# Stepper_Test.net
KiCad netlist of a schematic drawn in EAGLE
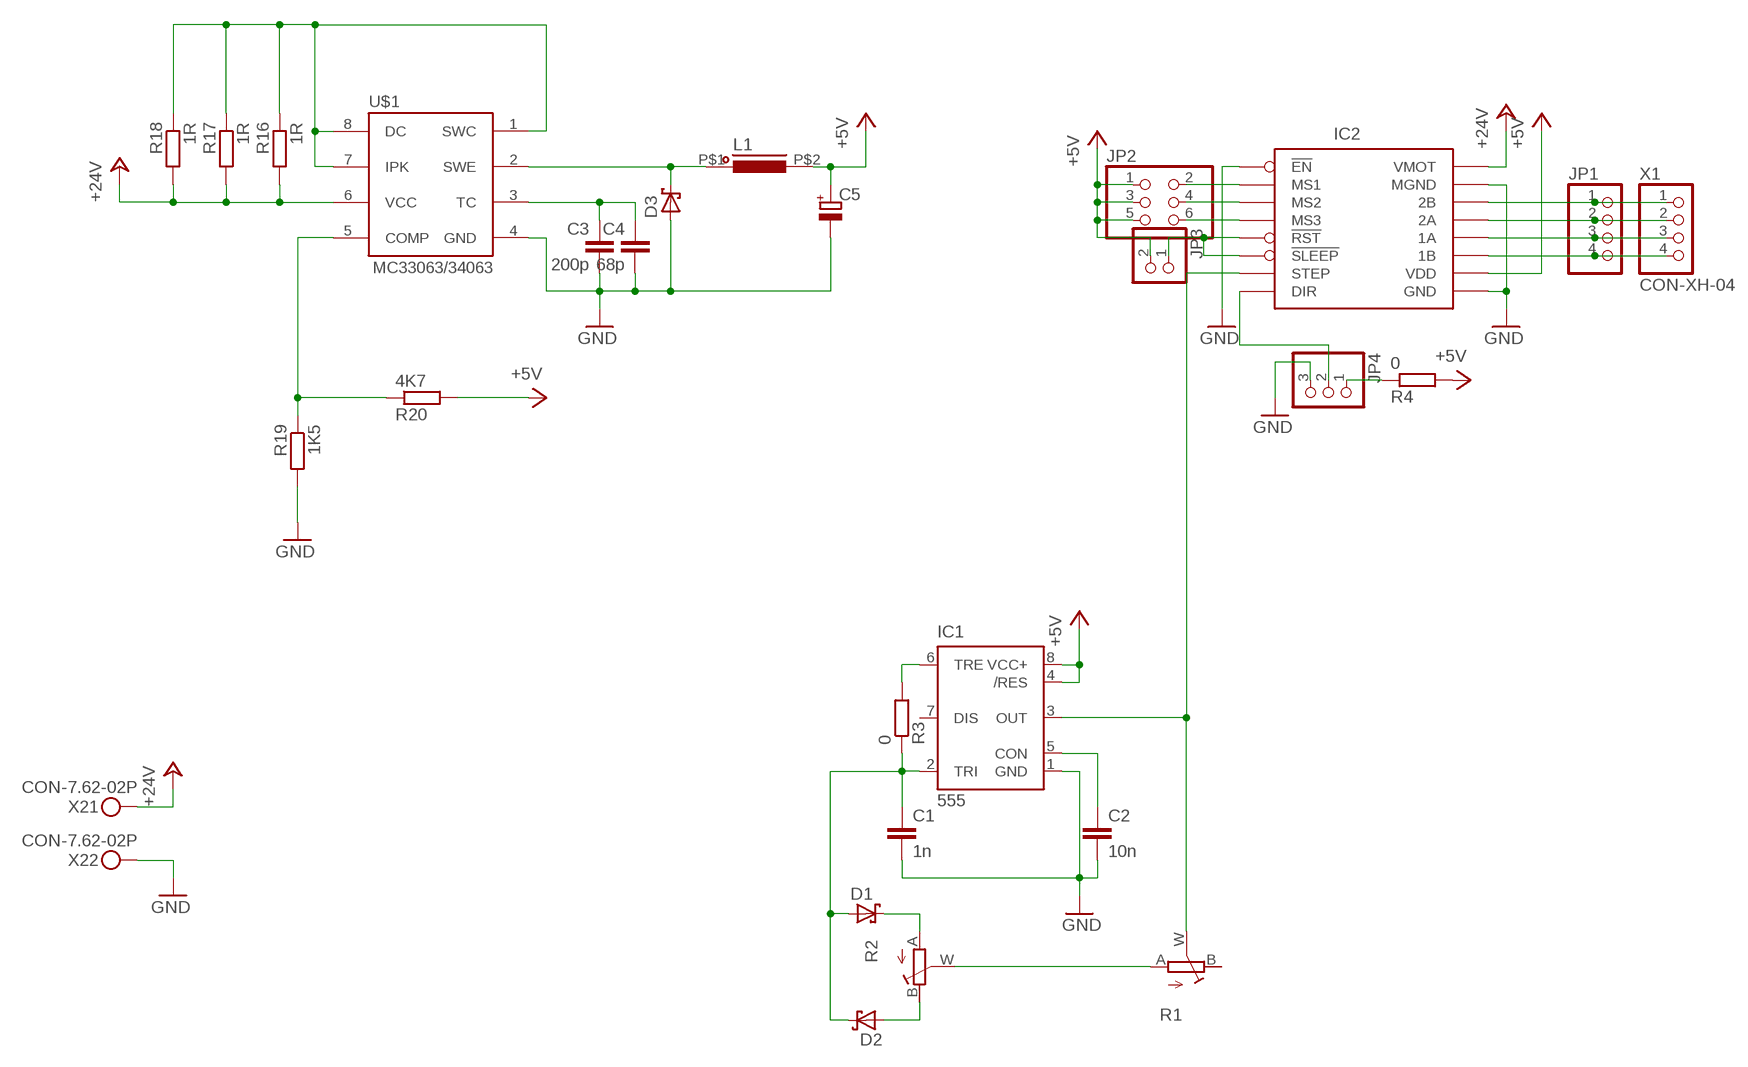
[diagram p0: schematic, sheet 1]

(export (version "E")
  (design (tool "Eeschema 10.0.6"))
  (components
    (comp (ref "C1")
      (value "1n")
      (footprint "eagle-import:C0805")
      (libsource (lib "eagle-import") (part "CAP_0805"))
    )
    (comp (ref "C2")
      (value "10n")
      (footprint "eagle-import:C0805")
      (libsource (lib "eagle-import") (part "CAP_0805"))
    )
    (comp (ref "C3")
      (value "200p")
      (footprint "eagle-import:C0805")
      (libsource (lib "eagle-import") (part "Namenlos_CAP_0805"))
    )
    (comp (ref "C4")
      (value "68p")
      (footprint "eagle-import:C0805")
      (libsource (lib "eagle-import") (part "Namenlos_CAP_0805"))
    )
    (comp (ref "C5")
      (value "CAP-POL_E3.5-8")
      (footprint "eagle-import:E3,5-8")
      (libsource (lib "eagle-import") (part "CAP-POL_E3.5-8"))
    )
    (comp (ref "D1")
      (value "DIODE-SH_SOD523")
      (footprint "eagle-import:SOD523")
      (libsource (lib "eagle-import") (part "DIODE-SH_SOD523"))
    )
    (comp (ref "D2")
      (value "DIODE-SH_SOD523")
      (footprint "eagle-import:SOD523")
      (libsource (lib "eagle-import") (part "DIODE-SH_SOD523"))
    )
    (comp (ref "D3")
      (value "DIODE-SH_SMA")
      (footprint "eagle-import:DO214AC")
      (libsource (lib "eagle-import") (part "Namenlos_DIODE-SH_SMA"))
    )
    (comp (ref "IC1")
      (value "555")
      (footprint "eagle-import:SO08")
      (libsource (lib "eagle-import") (part "555D"))
    )
    (comp (ref "IC2")
      (value "STEP-DRV")
      (footprint "eagle-import:DRV-BRK")
      (libsource (lib "eagle-import") (part "STEP-DRV"))
    )
    (comp (ref "JP1")
      (value "PINHD-1X4")
      (footprint "eagle-import:1X04")
      (libsource (lib "eagle-import") (part "PINHD-1X4"))
    )
    (comp (ref "JP2")
      (value "PINHD-2X3")
      (footprint "eagle-import:2X03")
      (libsource (lib "eagle-import") (part "PINHD-2X3"))
    )
    (comp (ref "JP3")
      (value "PINHD-1X2")
      (footprint "eagle-import:1X02")
      (libsource (lib "eagle-import") (part "PINHD-1X2"))
    )
    (comp (ref "JP4")
      (value "PINHD-1X3")
      (footprint "eagle-import:1X03")
      (libsource (lib "eagle-import") (part "PINHD-1X3"))
    )
    (comp (ref "L1")
      (value "INDUCTORCW68")
      (footprint "eagle-import:CW68")
      (libsource (lib "eagle-import") (part "INDUCTORCW68"))
    )
    (comp (ref "R1")
      (value "R_POTTURN-X")
      (footprint "eagle-import:RJ9W")
      (libsource (lib "eagle-import") (part "R_POTTURN-X"))
    )
    (comp (ref "R2")
      (value "R_POTTURN-X")
      (footprint "eagle-import:RJ9W")
      (libsource (lib "eagle-import") (part "R_POTTURN-X"))
    )
    (comp (ref "R3")
      (value "0")
      (footprint "eagle-import:R0805")
      (libsource (lib "eagle-import") (part "R_0805"))
    )
    (comp (ref "R4")
      (value "0")
      (footprint "eagle-import:R0805")
      (libsource (lib "eagle-import") (part "R_0805"))
    )
    (comp (ref "R16")
      (value "1R")
      (footprint "eagle-import:R0805")
      (libsource (lib "eagle-import") (part "R_0805"))
    )
    (comp (ref "R17")
      (value "1R")
      (footprint "eagle-import:R0805")
      (libsource (lib "eagle-import") (part "R_0805"))
    )
    (comp (ref "R18")
      (value "1R")
      (footprint "eagle-import:R0805")
      (libsource (lib "eagle-import") (part "R_0805"))
    )
    (comp (ref "R19")
      (value "1K5")
      (footprint "eagle-import:R0805")
      (libsource (lib "eagle-import") (part "R_0805"))
    )
    (comp (ref "R20")
      (value "4K7")
      (footprint "eagle-import:R0805")
      (libsource (lib "eagle-import") (part "R_0805"))
    )
    (comp (ref "U$1")
      (value "MC33063/MC34063P")
      (footprint "eagle-import:DIL08")
      (libsource (lib "eagle-import") (part "MC33063/MC34063P"))
    )
    (comp (ref "X1")
      (value "CON-XH-04")
      (footprint "eagle-import:XH-04")
      (libsource (lib "eagle-import") (part "CON-XH-04"))
    )
    (comp (ref "X2")
      (value "CON-7.62-02P")
      (footprint "eagle-import:KF25C-7.62-02P-13")
      (libsource (lib "eagle-import") (part "CON-7.62-02P"))
    )
  )
  (nets
    (net (code "1") (name "+5V") (class "Default")
      (node (ref "C5") (pin "+") (pinfunction "+_+") (pintype "passive"))
      (node (ref "IC1") (pin "4") (pinfunction "/RES_4") (pintype "input"))
      (node (ref "IC1") (pin "8") (pinfunction "VCC+_8") (pintype "power_in"))
      (node (ref "IC2") (pin "P$10") (pinfunction "VDD_P$10") (pintype "bidirectional"))
      (node (ref "JP2") (pin "1") (pinfunction "1_1") (pintype "passive"))
      (node (ref "JP2") (pin "3") (pinfunction "3_3") (pintype "passive"))
      (node (ref "JP2") (pin "5") (pinfunction "5_5") (pintype "passive"))
      (node (ref "JP3") (pin "2") (pinfunction "2_2") (pintype "passive"))
      (node (ref "L1") (pin "P$2") (pinfunction "2_P$2") (pintype "passive"))
      (node (ref "R20") (pin "2") (pinfunction "2_2") (pintype "passive"))
      (node (ref "R4") (pin "2") (pinfunction "2_2") (pintype "passive"))
    )
    (net (code "2") (name "+24V") (class "Default")
      (node (ref "IC2") (pin "P$16") (pinfunction "VMOT_P$16") (pintype "bidirectional"))
      (node (ref "R16") (pin "2") (pinfunction "2_2") (pintype "passive"))
      (node (ref "R17") (pin "2") (pinfunction "2_2") (pintype "passive"))
      (node (ref "R18") (pin "2") (pinfunction "2_2") (pintype "passive"))
      (node (ref "U$1") (pin "6") (pinfunction "VCC_6") (pintype "power_in"))
      (node (ref "X2") (pin "P$1") (pinfunction "KL_P$1") (pintype "passive"))
    )
    (net (code "3") (name "GND") (class "Default")
      (node (ref "C1") (pin "2") (pinfunction "2_2") (pintype "passive"))
      (node (ref "C2") (pin "2") (pinfunction "2_2") (pintype "passive"))
      (node (ref "C3") (pin "2") (pinfunction "2_2") (pintype "passive"))
      (node (ref "C4") (pin "2") (pinfunction "2_2") (pintype "passive"))
      (node (ref "C5") (pin "-") (pinfunction "-_-") (pintype "passive"))
      (node (ref "D3") (pin "A") (pinfunction "A_A") (pintype "passive"))
      (node (ref "IC1") (pin "1") (pinfunction "GND_1") (pintype "power_in"))
      (node (ref "IC2") (pin "P$1") (pinfunction "~{EN}_P$1") (pintype "bidirectional"))
      (node (ref "IC2") (pin "P$15") (pinfunction "MGND_P$15") (pintype "bidirectional"))
      (node (ref "IC2") (pin "P$9") (pinfunction "GND_P$9") (pintype "bidirectional"))
      (node (ref "JP4") (pin "3") (pinfunction "3_3") (pintype "passive"))
      (node (ref "R19") (pin "2") (pinfunction "2_2") (pintype "passive"))
      (node (ref "U$1") (pin "4") (pinfunction "GND_4") (pintype "power_in"))
      (node (ref "X2") (pin "P$2") (pinfunction "KL_P$2") (pintype "passive"))
    )
    (net (code "4") (name "Net-(D1-PadC)") (class "Default")
      (node (ref "D1") (pin "C") (pinfunction "C_C") (pintype "passive"))
      (node (ref "R2") (pin "A") (pinfunction "A_A") (pintype "passive"))
    )
    (net (code "5") (name "Net-(IC1-CON)") (class "Default")
      (node (ref "C2") (pin "1") (pinfunction "1_1") (pintype "passive"))
      (node (ref "IC1") (pin "5") (pinfunction "CON_5") (pintype "input"))
    )
    (net (code "6") (name "Net-(IC1-OUT)") (class "Default")
      (node (ref "IC1") (pin "3") (pinfunction "OUT_3") (pintype "output"))
      (node (ref "IC2") (pin "P$7") (pinfunction "STEP_P$7") (pintype "bidirectional"))
      (node (ref "R1") (pin "W") (pinfunction "S_W") (pintype "passive"))
    )
    (net (code "7") (name "Net-(IC1-TRE)") (class "Default")
      (node (ref "IC1") (pin "6") (pinfunction "TRE_6") (pintype "input"))
      (node (ref "R3") (pin "2") (pinfunction "2_2") (pintype "passive"))
    )
    (net (code "8") (name "Net-(IC1-TRI)") (class "Default")
      (node (ref "C1") (pin "1") (pinfunction "1_1") (pintype "passive"))
      (node (ref "D1") (pin "A") (pinfunction "A_A") (pintype "passive"))
      (node (ref "D2") (pin "C") (pinfunction "C_C") (pintype "passive"))
      (node (ref "IC1") (pin "2") (pinfunction "TRI_2") (pintype "input"))
      (node (ref "R3") (pin "1") (pinfunction "1_1") (pintype "passive"))
    )
    (net (code "9") (name "Net-(IC2-1A)") (class "Default")
      (node (ref "IC2") (pin "P$12") (pinfunction "1A_P$12") (pintype "bidirectional"))
      (node (ref "JP1") (pin "3") (pinfunction "3_3") (pintype "passive"))
      (node (ref "X1") (pin "3") (pinfunction "3_3") (pintype "passive"))
    )
    (net (code "10") (name "Net-(IC2-1B)") (class "Default")
      (node (ref "IC2") (pin "P$11") (pinfunction "1B_P$11") (pintype "bidirectional"))
      (node (ref "JP1") (pin "4") (pinfunction "4_4") (pintype "passive"))
      (node (ref "X1") (pin "4") (pinfunction "4_4") (pintype "passive"))
    )
    (net (code "11") (name "Net-(IC2-2A)") (class "Default")
      (node (ref "IC2") (pin "P$13") (pinfunction "2A_P$13") (pintype "bidirectional"))
      (node (ref "JP1") (pin "2") (pinfunction "2_2") (pintype "passive"))
      (node (ref "X1") (pin "2") (pinfunction "2_2") (pintype "passive"))
    )
    (net (code "12") (name "Net-(IC2-2B)") (class "Default")
      (node (ref "IC2") (pin "P$14") (pinfunction "2B_P$14") (pintype "bidirectional"))
      (node (ref "JP1") (pin "1") (pinfunction "1_1") (pintype "passive"))
      (node (ref "X1") (pin "1") (pinfunction "1_1") (pintype "passive"))
    )
    (net (code "13") (name "Net-(IC2-DIR)") (class "Default")
      (node (ref "IC2") (pin "P$8") (pinfunction "DIR_P$8") (pintype "bidirectional"))
      (node (ref "JP4") (pin "2") (pinfunction "2_2") (pintype "passive"))
    )
    (net (code "14") (name "Net-(IC2-MS1)") (class "Default")
      (node (ref "IC2") (pin "P$2") (pinfunction "MS1_P$2") (pintype "bidirectional"))
      (node (ref "JP2") (pin "2") (pinfunction "2_2") (pintype "passive"))
    )
    (net (code "15") (name "Net-(IC2-MS2)") (class "Default")
      (node (ref "IC2") (pin "P$3") (pinfunction "MS2_P$3") (pintype "bidirectional"))
      (node (ref "JP2") (pin "4") (pinfunction "4_4") (pintype "passive"))
    )
    (net (code "16") (name "Net-(IC2-MS3)") (class "Default")
      (node (ref "IC2") (pin "P$4") (pinfunction "MS3_P$4") (pintype "bidirectional"))
      (node (ref "JP2") (pin "6") (pinfunction "6_6") (pintype "passive"))
    )
    (net (code "17") (name "Net-(IC2-~{RST})") (class "Default")
      (node (ref "IC2") (pin "P$5") (pinfunction "~{RST}_P$5") (pintype "bidirectional"))
      (node (ref "IC2") (pin "P$6") (pinfunction "~{SLEEP}_P$6") (pintype "bidirectional"))
      (node (ref "JP3") (pin "1") (pinfunction "1_1") (pintype "passive"))
    )
    (net (code "18") (name "Net-(JP4-Pad1)") (class "Default")
      (node (ref "JP4") (pin "1") (pinfunction "1_1") (pintype "passive"))
      (node (ref "R4") (pin "1") (pinfunction "1_1") (pintype "passive"))
    )
    (net (code "19") (name "Net-(L1-1)") (class "Default")
      (node (ref "D3") (pin "C") (pinfunction "C_C") (pintype "passive"))
      (node (ref "L1") (pin "P$1") (pinfunction "1_P$1") (pintype "passive"))
      (node (ref "U$1") (pin "2") (pinfunction "SWE_2") (pintype "input"))
    )
    (net (code "20") (name "Net-(R2-E)") (class "Default")
      (node (ref "D2") (pin "A") (pinfunction "A_A") (pintype "passive"))
      (node (ref "R2") (pin "B") (pinfunction "E_B") (pintype "passive"))
    )
    (net (code "21") (name "Net-(R2-S)") (class "Default")
      (node (ref "R1") (pin "A") (pinfunction "A_A") (pintype "passive"))
      (node (ref "R2") (pin "W") (pinfunction "S_W") (pintype "passive"))
    )
    (net (code "22") (name "Net-(U$1-COMP)") (class "Default")
      (node (ref "R19") (pin "1") (pinfunction "1_1") (pintype "passive"))
      (node (ref "R20") (pin "1") (pinfunction "1_1") (pintype "passive"))
      (node (ref "U$1") (pin "5") (pinfunction "COMP_5") (pintype "input"))
    )
    (net (code "23") (name "Net-(U$1-DC)") (class "Default")
      (node (ref "R16") (pin "1") (pinfunction "1_1") (pintype "passive"))
      (node (ref "R17") (pin "1") (pinfunction "1_1") (pintype "passive"))
      (node (ref "R18") (pin "1") (pinfunction "1_1") (pintype "passive"))
      (node (ref "U$1") (pin "1") (pinfunction "SWC_1") (pintype "input"))
      (node (ref "U$1") (pin "7") (pinfunction "IPK_7") (pintype "bidirectional"))
      (node (ref "U$1") (pin "8") (pinfunction "DC_8") (pintype "input"))
    )
    (net (code "24") (name "Net-(U$1-TC)") (class "Default")
      (node (ref "C3") (pin "1") (pinfunction "1_1") (pintype "passive"))
      (node (ref "C4") (pin "1") (pinfunction "1_1") (pintype "passive"))
      (node (ref "U$1") (pin "3") (pinfunction "TC_3") (pintype "input"))
    )
    (net (code "25") (name "unconnected-(IC1-DIS-Pad7)") (class "Default")
      (node (ref "IC1") (pin "7") (pinfunction "DIS_7") (pintype "input"))
    )
    (net (code "26") (name "unconnected-(R1-E-PadB)") (class "Default")
      (node (ref "R1") (pin "B") (pinfunction "E_B") (pintype "passive"))
    )
  )
)
